# Pico-2-Max.net
KiCad netlist of a schematic drawn in EasyEDA Pro
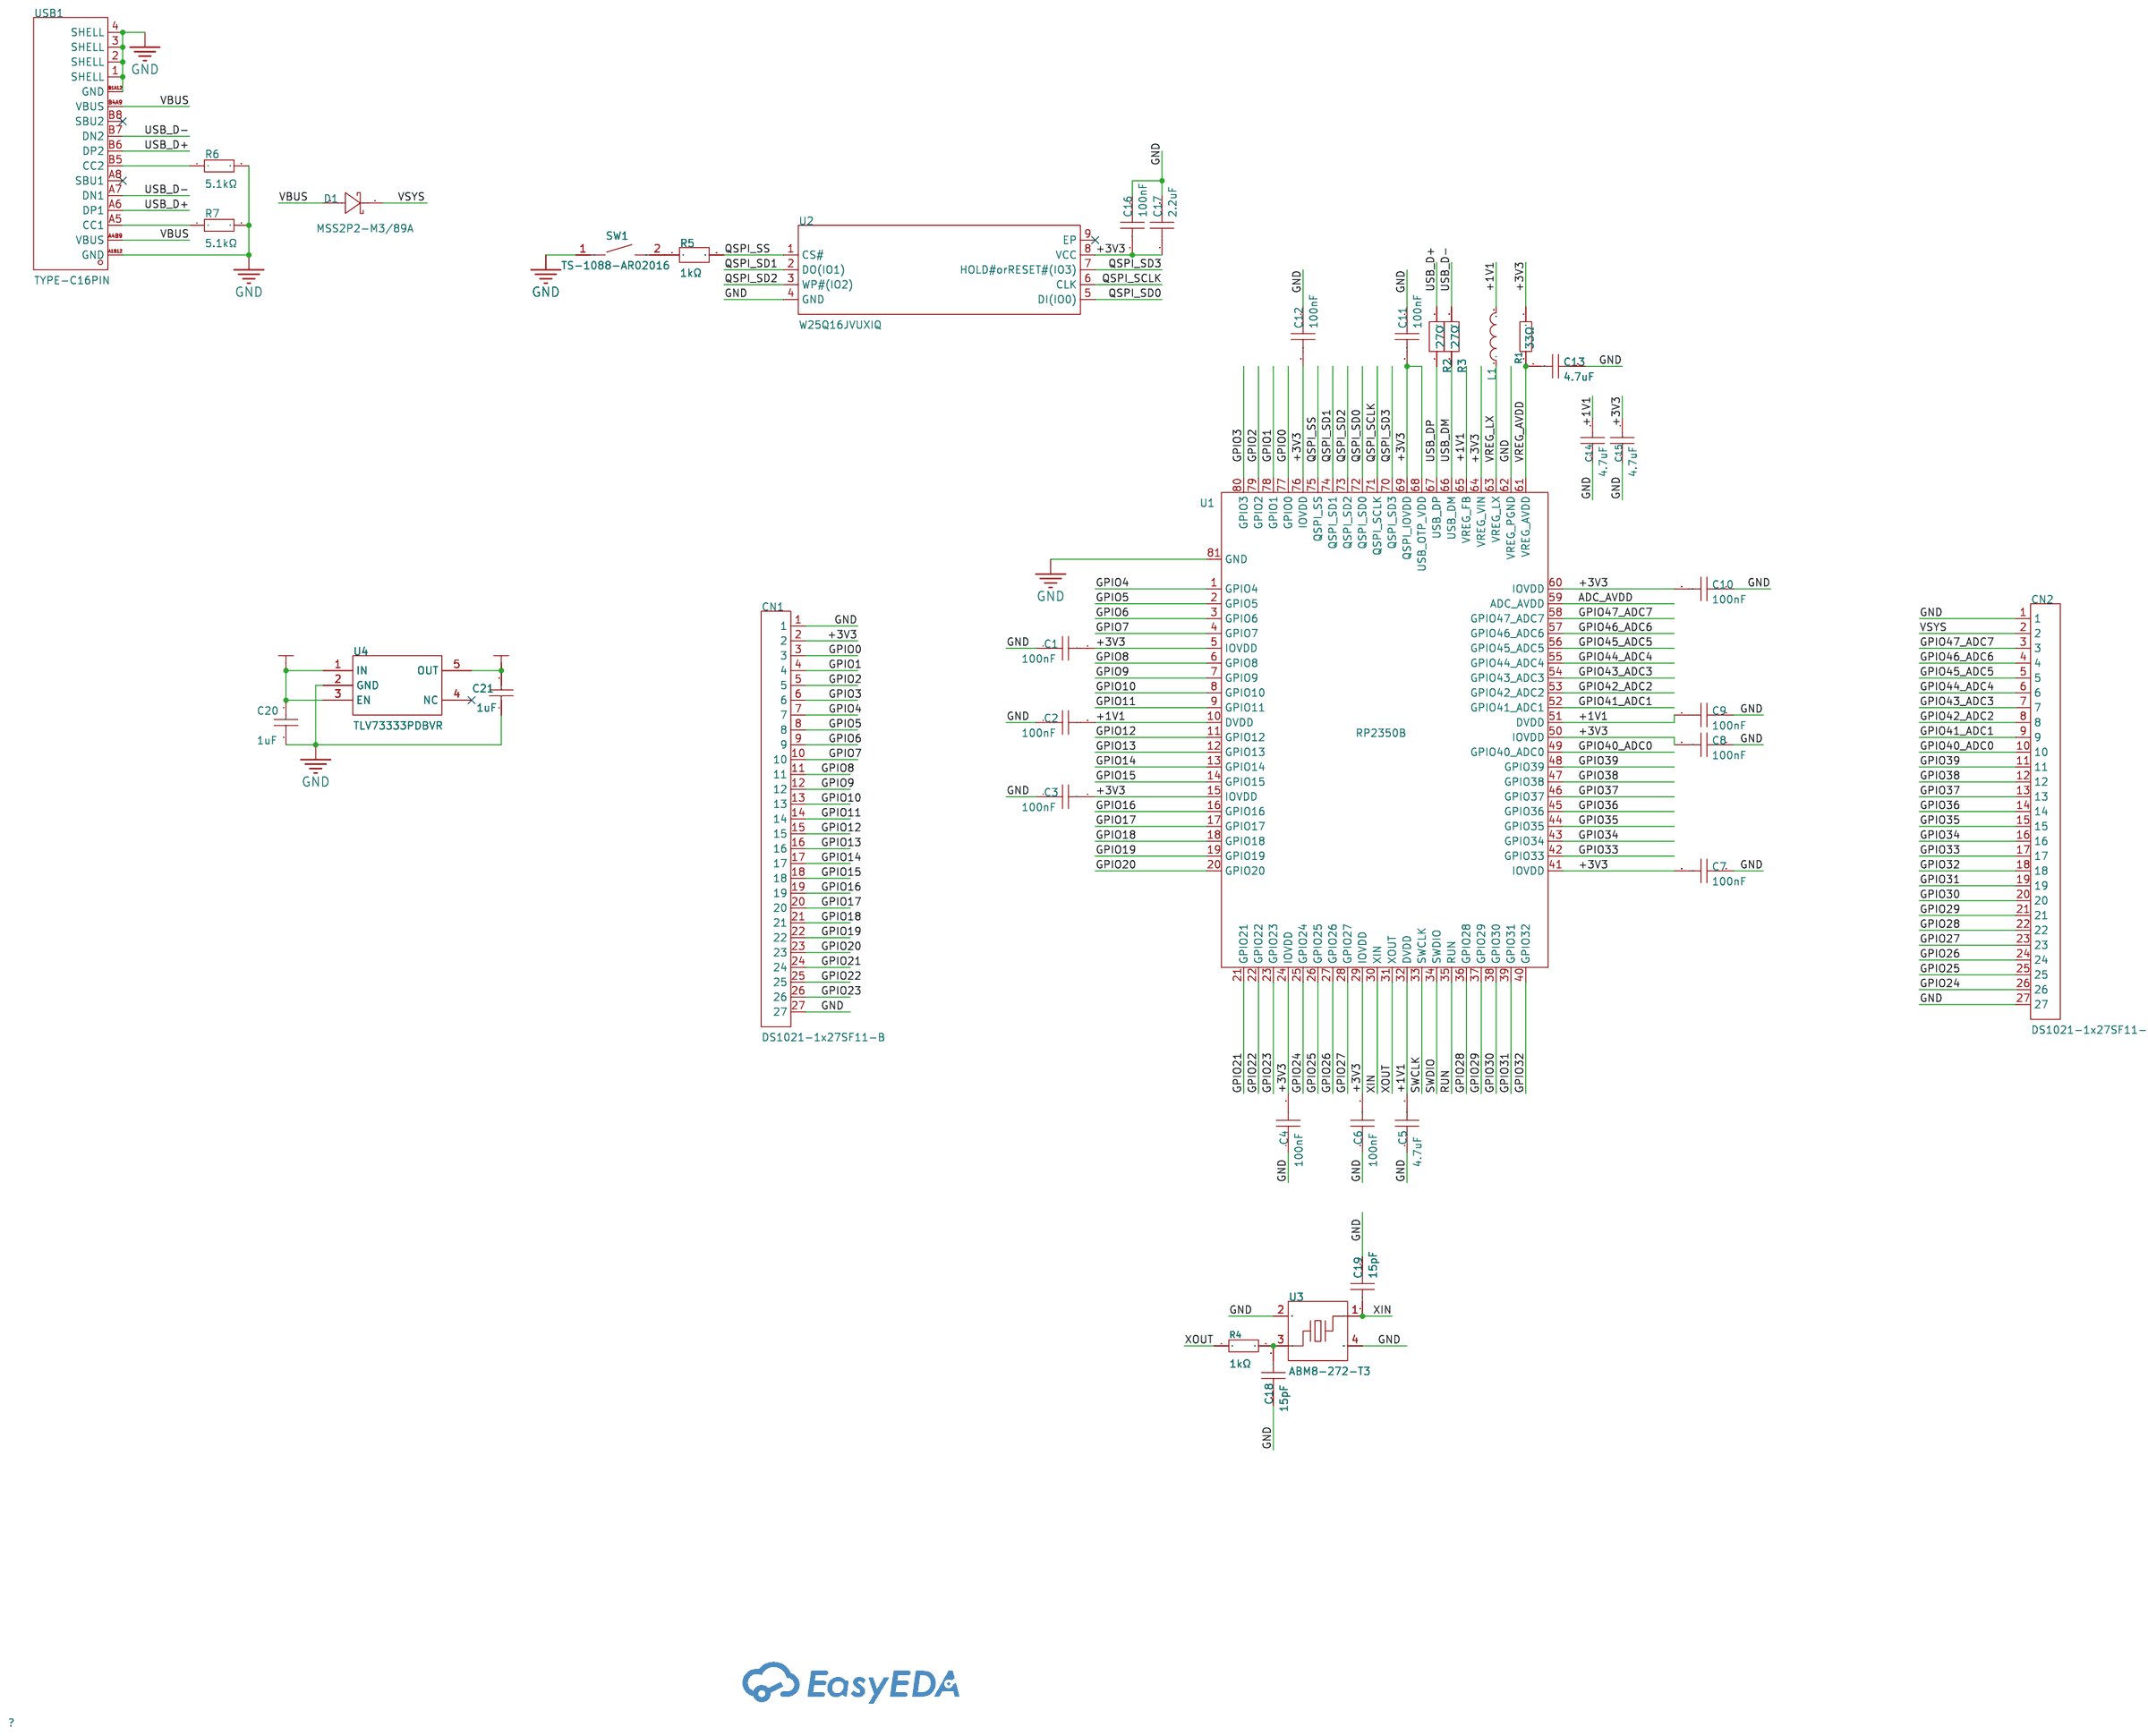
[diagram p0: schematic sheet]

(export (version "E")
  (design (tool "Eeschema 10.0.6"))
  (components
    (comp (ref "C1")
      (value "100nF")
      (footprint "easyedapro:C0201")
      (fields
        (field (name "Manufacturer Part") "GRM033R60J104KE19D")
        (field (name "Manufacturer") "muRata(村田)")
      )
      (libsource (lib "easyedapro") (part "GRM033R60J104KE19D"))
    )
    (comp (ref "C2")
      (value "100nF")
      (footprint "easyedapro:C0201")
      (fields
        (field (name "Manufacturer Part") "GRM033R60J104KE19D")
        (field (name "Manufacturer") "muRata(村田)")
      )
      (libsource (lib "easyedapro") (part "GRM033R60J104KE19D"))
    )
    (comp (ref "C3")
      (value "100nF")
      (footprint "easyedapro:C0201")
      (fields
        (field (name "Manufacturer Part") "GRM033R60J104KE19D")
        (field (name "Manufacturer") "muRata(村田)")
      )
      (libsource (lib "easyedapro") (part "GRM033R60J104KE19D"))
    )
    (comp (ref "C4")
      (value "100nF")
      (footprint "easyedapro:C0201")
      (fields
        (field (name "Manufacturer Part") "GRM033R60J104KE19D")
        (field (name "Manufacturer") "muRata(村田)")
      )
      (libsource (lib "easyedapro") (part "GRM033R60J104KE19D"))
    )
    (comp (ref "C5")
      (value "4.7uF")
      (footprint "easyedapro:C0201")
      (description "Capacitance:4.7uF Tolerance:±20% Tolerance:±20% Voltage Rating:6.3V Temperature Coefficient:X5R")
      (fields
        (field (name "Manufacturer Part") "GRM035R60J475ME15D")
        (field (name "Manufacturer") "muRata(村田)")
      )
      (libsource (lib "easyedapro") (part "GRM035R60J475ME15D"))
    )
    (comp (ref "C6")
      (value "100nF")
      (footprint "easyedapro:C0201")
      (fields
        (field (name "Manufacturer Part") "GRM033R60J104KE19D")
        (field (name "Manufacturer") "muRata(村田)")
      )
      (libsource (lib "easyedapro") (part "GRM033R60J104KE19D"))
    )
    (comp (ref "C7")
      (value "100nF")
      (footprint "easyedapro:C0201")
      (fields
        (field (name "Manufacturer Part") "GRM033R60J104KE19D")
        (field (name "Manufacturer") "muRata(村田)")
      )
      (libsource (lib "easyedapro") (part "GRM033R60J104KE19D"))
    )
    (comp (ref "C8")
      (value "100nF")
      (footprint "easyedapro:C0201")
      (fields
        (field (name "Manufacturer Part") "GRM033R60J104KE19D")
        (field (name "Manufacturer") "muRata(村田)")
      )
      (libsource (lib "easyedapro") (part "GRM033R60J104KE19D"))
    )
    (comp (ref "C9")
      (value "100nF")
      (footprint "easyedapro:C0201")
      (fields
        (field (name "Manufacturer Part") "GRM033R60J104KE19D")
        (field (name "Manufacturer") "muRata(村田)")
      )
      (libsource (lib "easyedapro") (part "GRM033R60J104KE19D"))
    )
    (comp (ref "C10")
      (value "100nF")
      (footprint "easyedapro:C0201")
      (fields
        (field (name "Manufacturer Part") "GRM033R60J104KE19D")
        (field (name "Manufacturer") "muRata(村田)")
      )
      (libsource (lib "easyedapro") (part "GRM033R60J104KE19D"))
    )
    (comp (ref "C11")
      (value "100nF")
      (footprint "easyedapro:C0201")
      (fields
        (field (name "Manufacturer Part") "GRM033R60J104KE19D")
        (field (name "Manufacturer") "muRata(村田)")
      )
      (libsource (lib "easyedapro") (part "GRM033R60J104KE19D"))
    )
    (comp (ref "C12")
      (value "100nF")
      (footprint "easyedapro:C0201")
      (fields
        (field (name "Manufacturer Part") "GRM033R60J104KE19D")
        (field (name "Manufacturer") "muRata(村田)")
      )
      (libsource (lib "easyedapro") (part "GRM033R60J104KE19D"))
    )
    (comp (ref "C13")
      (value "4.7uF")
      (footprint "easyedapro:C0201")
      (description "Capacitance:4.7uF Tolerance:±20% Tolerance:±20% Voltage Rating:6.3V Temperature Coefficient:X5R")
      (fields
        (field (name "Manufacturer Part") "GRM035R60J475ME15D")
        (field (name "Manufacturer") "muRata(村田)")
      )
      (libsource (lib "easyedapro") (part "GRM035R60J475ME15D"))
    )
    (comp (ref "C14")
      (value "4.7uF")
      (footprint "easyedapro:C0402")
      (description "Capacitance:4.7uF Tolerance:±20% Tolerance:±20% Voltage Rating:10V Temperature Coefficient:X5R")
      (fields
        (field (name "Manufacturer Part") "CL05A475MP5NRNC")
        (field (name "Manufacturer") "SAMSUNG(三星)")
      )
      (libsource (lib "easyedapro") (part "CL05A475MP5NRNC"))
    )
    (comp (ref "C15")
      (value "4.7uF")
      (footprint "easyedapro:C0402")
      (description "Capacitance:4.7uF Tolerance:±20% Tolerance:±20% Voltage Rating:10V Temperature Coefficient:X5R")
      (fields
        (field (name "Manufacturer Part") "CL05A475MP5NRNC")
        (field (name "Manufacturer") "SAMSUNG(三星)")
      )
      (libsource (lib "easyedapro") (part "CL05A475MP5NRNC"))
    )
    (comp (ref "C16")
      (value "100nF")
      (footprint "easyedapro:C0201")
      (fields
        (field (name "Manufacturer Part") "GRM033R60J104KE19D")
        (field (name "Manufacturer") "muRata(村田)")
      )
      (libsource (lib "easyedapro") (part "GRM033R60J104KE19D"))
    )
    (comp (ref "C17")
      (value "2.2uF")
      (footprint "easyedapro:C0201")
      (description "Capacitance:2.2uF Tolerance:±20% Tolerance:±20% Voltage Rating:6.3V Temperature Coefficient:X5R")
      (fields (field (name "Manufacturer Part") "0201X225M6R3NT") (field (name "Manufacturer") "FH(风华)"))
      (libsource (lib "easyedapro") (part "0201X225M6R3NT"))
    )
    (comp (ref "C18")
      (value "15pF")
      (footprint "easyedapro:C0201")
      (fields
        (field (name "Manufacturer Part") "CC0201JRNPO9BN150")
        (field (name "Manufacturer") "YAGEO(国巨)")
      )
      (libsource (lib "easyedapro") (part "CC0201JRNPO9BN150"))
    )
    (comp (ref "C19")
      (value "15pF")
      (footprint "easyedapro:C0201")
      (fields
        (field (name "Manufacturer Part") "CC0201JRNPO9BN150")
        (field (name "Manufacturer") "YAGEO(国巨)")
      )
      (libsource (lib "easyedapro") (part "CC0201JRNPO9BN150"))
    )
    (comp (ref "C20")
      (value "1uF")
      (footprint "easyedapro:C0201")
      (description "Capacitance:1uF Tolerance:±20% Tolerance:±20% Voltage Rating:6.3V Temperature Coefficient:X5R")
      (fields
        (field (name "Manufacturer Part") "CL03A105MQ3CSNH")
        (field (name "Manufacturer") "SAMSUNG(三星)")
      )
      (libsource (lib "easyedapro") (part "CL03A105MQ3CSNH"))
    )
    (comp (ref "C21")
      (value "1uF")
      (footprint "easyedapro:C0201")
      (description "Capacitance:1uF Tolerance:±20% Tolerance:±20% Voltage Rating:6.3V Temperature Coefficient:X5R")
      (fields
        (field (name "Manufacturer Part") "CL03A105MQ3CSNH")
        (field (name "Manufacturer") "SAMSUNG(三星)")
      )
      (libsource (lib "easyedapro") (part "CL03A105MQ3CSNH"))
    )
    (comp (ref "CN1")
      (value "DS1021-1x27SF11-B")
      (footprint "easyedapro:HDR-TH_27P-P2.54-V-M")
      (fields (field (name "Manufacturer") "CONNFLY"))
      (libsource (lib "easyedapro") (part "DS1021-1X27SF11-B"))
    )
    (comp (ref "CN2")
      (value "DS1021-1x27SF11-B")
      (footprint "easyedapro:HDR-TH_27P-P2.54-V-M")
      (fields (field (name "Manufacturer") "CONNFLY"))
      (libsource (lib "easyedapro") (part "DS1021-1X27SF11-B"))
    )
    (comp (ref "D1")
      (value "MSS2P2-M3/89A")
      (footprint "easyedapro:DO-219AD_L2.2-W1.3-L-RD_MSS2P2-M3-89A")
      (fields (field (name "Manufacturer") "VISHAY(威世)"))
      (libsource (lib "easyedapro") (part "MSS2P2-M3/89A"))
    )
    (comp (ref "L1")
      (value "AOTA-B201610S3R3-101-T")
      (footprint "easyedapro:IND-SMD_L2.0-W1.6_AOTA-B201610S3R3-101-T")
      (fields (field (name "Manufacturer") "ABRACON"))
      (libsource (lib "easyedapro") (part "AOTA-B201610S3R3-101-T"))
    )
    (comp (ref "R1")
      (value "33Ω")
      (footprint "easyedapro:R0201")
      (fields
        (field (name "Manufacturer Part") "0201WMJ0330TEE")
        (field (name "Manufacturer") "UNI-ROYAL(厚声)")
      )
      (libsource (lib "easyedapro") (part "0201WMJ0330TEE"))
    )
    (comp (ref "R2")
      (value "27Ω")
      (footprint "easyedapro:R0201")
      (fields
        (field (name "Manufacturer Part") "0201WMF270JTEE")
        (field (name "Manufacturer") "UNI-ROYAL(厚声)")
      )
      (libsource (lib "easyedapro") (part "0201WMF270JTEE"))
    )
    (comp (ref "R3")
      (value "27Ω")
      (footprint "easyedapro:R0201")
      (fields
        (field (name "Manufacturer Part") "0201WMF270JTEE")
        (field (name "Manufacturer") "UNI-ROYAL(厚声)")
      )
      (libsource (lib "easyedapro") (part "0201WMF270JTEE"))
    )
    (comp (ref "R4")
      (value "1kΩ")
      (footprint "easyedapro:R0201")
      (fields (field (name "Manufacturer Part") "RTT01102JTH") (field (name "Manufacturer") "RALEC(旺诠)"))
      (libsource (lib "easyedapro") (part "RTT01102JTH"))
    )
    (comp (ref "R5")
      (value "1kΩ")
      (footprint "easyedapro:R0201")
      (fields (field (name "Manufacturer Part") "FRC0201F1001TS") (field (name "Manufacturer") "FOJAN(富捷)"))
      (libsource (lib "easyedapro") (part "FRC0201F1001TS"))
    )
    (comp (ref "R6")
      (value "5.1kΩ")
      (footprint "easyedapro:R0201")
      (fields (field (name "Manufacturer Part") "RC0201FR-075K1L") (field (name "Manufacturer") "YAGEO(国巨)"))
      (libsource (lib "easyedapro") (part "RC0201FR-075K1L"))
    )
    (comp (ref "R7")
      (value "5.1kΩ")
      (footprint "easyedapro:R0201")
      (fields (field (name "Manufacturer Part") "RC0201FR-075K1L") (field (name "Manufacturer") "YAGEO(国巨)"))
      (libsource (lib "easyedapro") (part "RC0201FR-075K1L"))
    )
    (comp (ref "SW1")
      (value "TS-1088-AR02016")
      (footprint "easyedapro:SW-SMD_L3.9-W3.0-P4.45")
      (fields (field (name "Manufacturer") "XUNPU(讯普)"))
      (libsource (lib "easyedapro") (part "TS-1088-AR02016"))
    )
    (comp (ref "U1")
      (value "RP2350B")
      (footprint "easyedapro:QFN-80_L10.0-W10.0-P0.40-TL-EP3.4")
      (fields (field (name "Manufacturer") "Raspberry Pi(树莓派)"))
      (libsource (lib "easyedapro") (part "RP2350B_C42415655"))
    )
    (comp (ref "U2")
      (value "W25Q16JVUXIQ")
      (footprint "easyedapro:USON-8_L3.0-W2.0-P0.50-BL-EP")
      (fields (field (name "Manufacturer") "Winbond(华邦)"))
      (libsource (lib "easyedapro") (part "W25Q16JVUXIQ"))
    )
    (comp (ref "U3")
      (value "ABM8-272-T3")
      (footprint "easyedapro:CRYSTAL-SMD_4P-L3.2-W2.5-BL")
      (fields (field (name "Manufacturer") "ABRACON"))
      (libsource (lib "easyedapro") (part "ABM8-272-T3_C20625731"))
    )
    (comp (ref "U4")
      (value "TLV73333PDBVR")
      (footprint "easyedapro:SOT-23-5_L3.0-W1.7-P0.95-LS2.8-BR")
      (fields (field (name "Manufacturer") "TI(德州仪器)"))
      (libsource (lib "easyedapro") (part "TLV73333PDBVR"))
    )
    (comp (ref "USB1")
      (value "TYPE-C16PIN")
      (footprint "easyedapro:USB-C-SMD_TYPE-C16PIN")
      (fields (field (name "Manufacturer") "SHOU HAN(首韩)"))
      (libsource (lib "easyedapro") (part "TYPE-C16PIN"))
    )
  )
  (nets
    (net (code "1") (name "+3V3") (class "Default")
      (node (ref "C1") (pin "2") (pinfunction "2_2") (pintype "unspecified"))
      (node (ref "C10") (pin "2") (pinfunction "2_2") (pintype "unspecified"))
      (node (ref "C11") (pin "2") (pinfunction "2_2") (pintype "unspecified"))
      (node (ref "C12") (pin "2") (pinfunction "2_2") (pintype "unspecified"))
      (node (ref "C15") (pin "2") (pinfunction "2_2") (pintype "input"))
      (node (ref "C16") (pin "2") (pinfunction "2_2") (pintype "unspecified"))
      (node (ref "C17") (pin "1") (pinfunction "1_1") (pintype "unspecified"))
      (node (ref "C21") (pin "2") (pinfunction "2_2") (pintype "input"))
      (node (ref "C3") (pin "2") (pinfunction "2_2") (pintype "unspecified"))
      (node (ref "C4") (pin "2") (pinfunction "2_2") (pintype "unspecified"))
      (node (ref "C6") (pin "2") (pinfunction "2_2") (pintype "unspecified"))
      (node (ref "C7") (pin "2") (pinfunction "2_2") (pintype "unspecified"))
      (node (ref "C8") (pin "2") (pinfunction "2_2") (pintype "unspecified"))
      (node (ref "CN1") (pin "2") (pinfunction "2_2") (pintype "unspecified"))
      (node (ref "R1") (pin "2") (pinfunction "2_2") (pintype "input"))
      (node (ref "U1") (pin "15") (pinfunction "IOVDD_15") (pintype "unspecified"))
      (node (ref "U1") (pin "24") (pinfunction "IOVDD_24") (pintype "unspecified"))
      (node (ref "U1") (pin "29") (pinfunction "IOVDD_29") (pintype "unspecified"))
      (node (ref "U1") (pin "41") (pinfunction "IOVDD_41") (pintype "unspecified"))
      (node (ref "U1") (pin "5") (pinfunction "IOVDD_5") (pintype "unspecified"))
      (node (ref "U1") (pin "50") (pinfunction "IOVDD_50") (pintype "unspecified"))
      (node (ref "U1") (pin "60") (pinfunction "IOVDD_60") (pintype "unspecified"))
      (node (ref "U1") (pin "64") (pinfunction "VREG_VIN_64") (pintype "unspecified"))
      (node (ref "U1") (pin "68") (pinfunction "USB_OTP_VDD_68") (pintype "unspecified"))
      (node (ref "U1") (pin "69") (pinfunction "QSPI_IOVDD_69") (pintype "unspecified"))
      (node (ref "U1") (pin "76") (pinfunction "IOVDD_76") (pintype "unspecified"))
      (node (ref "U2") (pin "8") (pinfunction "VCC_8") (pintype "unspecified"))
      (node (ref "U4") (pin "5") (pinfunction "OUT_5") (pintype "unspecified"))
    )
    (net (code "2") (name "/+1V1") (class "Default")
      (node (ref "C14") (pin "2") (pinfunction "2_2") (pintype "input"))
      (node (ref "C2") (pin "2") (pinfunction "2_2") (pintype "unspecified"))
      (node (ref "C5") (pin "2") (pinfunction "2_2") (pintype "unspecified"))
      (node (ref "C9") (pin "2") (pinfunction "2_2") (pintype "unspecified"))
      (node (ref "L1") (pin "2") (pinfunction "2_2") (pintype "unspecified"))
      (node (ref "U1") (pin "10") (pinfunction "DVDD_10") (pintype "unspecified"))
      (node (ref "U1") (pin "32") (pinfunction "DVDD_32") (pintype "unspecified"))
      (node (ref "U1") (pin "51") (pinfunction "DVDD_51") (pintype "unspecified"))
      (node (ref "U1") (pin "65") (pinfunction "VREG_FB_65") (pintype "unspecified"))
    )
    (net (code "3") (name "/ADC_AVDD") (class "Default")
      (node (ref "U1") (pin "59") (pinfunction "ADC_AVDD_59") (pintype "unspecified"))
    )
    (net (code "4") (name "/GPIO0") (class "Default")
      (node (ref "CN1") (pin "3") (pinfunction "3_3") (pintype "unspecified"))
      (node (ref "U1") (pin "77") (pinfunction "GPIO0_77") (pintype "unspecified"))
    )
    (net (code "5") (name "/GPIO1") (class "Default")
      (node (ref "CN1") (pin "4") (pinfunction "4_4") (pintype "unspecified"))
      (node (ref "U1") (pin "78") (pinfunction "GPIO1_78") (pintype "unspecified"))
    )
    (net (code "6") (name "/GPIO2") (class "Default")
      (node (ref "CN1") (pin "5") (pinfunction "5_5") (pintype "unspecified"))
      (node (ref "U1") (pin "79") (pinfunction "GPIO2_79") (pintype "unspecified"))
    )
    (net (code "7") (name "/GPIO3") (class "Default")
      (node (ref "CN1") (pin "6") (pinfunction "6_6") (pintype "unspecified"))
      (node (ref "U1") (pin "80") (pinfunction "GPIO3_80") (pintype "unspecified"))
    )
    (net (code "8") (name "/GPIO4") (class "Default")
      (node (ref "CN1") (pin "7") (pinfunction "7_7") (pintype "unspecified"))
      (node (ref "U1") (pin "1") (pinfunction "GPIO4_1") (pintype "unspecified"))
    )
    (net (code "9") (name "/GPIO5") (class "Default")
      (node (ref "CN1") (pin "8") (pinfunction "8_8") (pintype "unspecified"))
      (node (ref "U1") (pin "2") (pinfunction "GPIO5_2") (pintype "unspecified"))
    )
    (net (code "10") (name "/GPIO6") (class "Default")
      (node (ref "CN1") (pin "9") (pinfunction "9_9") (pintype "unspecified"))
      (node (ref "U1") (pin "3") (pinfunction "GPIO6_3") (pintype "unspecified"))
    )
    (net (code "11") (name "/GPIO7") (class "Default")
      (node (ref "CN1") (pin "10") (pinfunction "10_10") (pintype "unspecified"))
      (node (ref "U1") (pin "4") (pinfunction "GPIO7_4") (pintype "unspecified"))
    )
    (net (code "12") (name "/GPIO8") (class "Default")
      (node (ref "CN1") (pin "11") (pinfunction "11_11") (pintype "unspecified"))
      (node (ref "U1") (pin "6") (pinfunction "GPIO8_6") (pintype "unspecified"))
    )
    (net (code "13") (name "/GPIO9") (class "Default")
      (node (ref "CN1") (pin "12") (pinfunction "12_12") (pintype "unspecified"))
      (node (ref "U1") (pin "7") (pinfunction "GPIO9_7") (pintype "unspecified"))
    )
    (net (code "14") (name "/GPIO10") (class "Default")
      (node (ref "CN1") (pin "13") (pinfunction "13_13") (pintype "unspecified"))
      (node (ref "U1") (pin "8") (pinfunction "GPIO10_8") (pintype "unspecified"))
    )
    (net (code "15") (name "/GPIO11") (class "Default")
      (node (ref "CN1") (pin "14") (pinfunction "14_14") (pintype "unspecified"))
      (node (ref "U1") (pin "9") (pinfunction "GPIO11_9") (pintype "unspecified"))
    )
    (net (code "16") (name "/GPIO12") (class "Default")
      (node (ref "CN1") (pin "15") (pinfunction "15_15") (pintype "unspecified"))
      (node (ref "U1") (pin "11") (pinfunction "GPIO12_11") (pintype "unspecified"))
    )
    (net (code "17") (name "/GPIO13") (class "Default")
      (node (ref "CN1") (pin "16") (pinfunction "16_16") (pintype "unspecified"))
      (node (ref "U1") (pin "12") (pinfunction "GPIO13_12") (pintype "unspecified"))
    )
    (net (code "18") (name "/GPIO14") (class "Default")
      (node (ref "CN1") (pin "17") (pinfunction "17_17") (pintype "unspecified"))
      (node (ref "U1") (pin "13") (pinfunction "GPIO14_13") (pintype "unspecified"))
    )
    (net (code "19") (name "/GPIO15") (class "Default")
      (node (ref "CN1") (pin "18") (pinfunction "18_18") (pintype "unspecified"))
      (node (ref "U1") (pin "14") (pinfunction "GPIO15_14") (pintype "unspecified"))
    )
    (net (code "20") (name "/GPIO16") (class "Default")
      (node (ref "CN1") (pin "19") (pinfunction "19_19") (pintype "unspecified"))
      (node (ref "U1") (pin "16") (pinfunction "GPIO16_16") (pintype "unspecified"))
    )
    (net (code "21") (name "/GPIO17") (class "Default")
      (node (ref "CN1") (pin "20") (pinfunction "20_20") (pintype "unspecified"))
      (node (ref "U1") (pin "17") (pinfunction "GPIO17_17") (pintype "unspecified"))
    )
    (net (code "22") (name "/GPIO18") (class "Default")
      (node (ref "CN1") (pin "21") (pinfunction "21_21") (pintype "unspecified"))
      (node (ref "U1") (pin "18") (pinfunction "GPIO18_18") (pintype "unspecified"))
    )
    (net (code "23") (name "/GPIO19") (class "Default")
      (node (ref "CN1") (pin "22") (pinfunction "22_22") (pintype "unspecified"))
      (node (ref "U1") (pin "19") (pinfunction "GPIO19_19") (pintype "unspecified"))
    )
    (net (code "24") (name "/GPIO20") (class "Default")
      (node (ref "CN1") (pin "23") (pinfunction "23_23") (pintype "unspecified"))
      (node (ref "U1") (pin "20") (pinfunction "GPIO20_20") (pintype "unspecified"))
    )
    (net (code "25") (name "/GPIO21") (class "Default")
      (node (ref "CN1") (pin "24") (pinfunction "24_24") (pintype "unspecified"))
      (node (ref "U1") (pin "21") (pinfunction "GPIO21_21") (pintype "unspecified"))
    )
    (net (code "26") (name "/GPIO22") (class "Default")
      (node (ref "CN1") (pin "25") (pinfunction "25_25") (pintype "unspecified"))
      (node (ref "U1") (pin "22") (pinfunction "GPIO22_22") (pintype "unspecified"))
    )
    (net (code "27") (name "/GPIO23") (class "Default")
      (node (ref "CN1") (pin "26") (pinfunction "26_26") (pintype "unspecified"))
      (node (ref "U1") (pin "23") (pinfunction "GPIO23_23") (pintype "unspecified"))
    )
    (net (code "28") (name "/GPIO24") (class "Default")
      (node (ref "CN2") (pin "26") (pinfunction "26_26") (pintype "unspecified"))
      (node (ref "U1") (pin "25") (pinfunction "GPIO24_25") (pintype "unspecified"))
    )
    (net (code "29") (name "/GPIO25") (class "Default")
      (node (ref "CN2") (pin "25") (pinfunction "25_25") (pintype "unspecified"))
      (node (ref "U1") (pin "26") (pinfunction "GPIO25_26") (pintype "unspecified"))
    )
    (net (code "30") (name "/GPIO26") (class "Default")
      (node (ref "CN2") (pin "24") (pinfunction "24_24") (pintype "unspecified"))
      (node (ref "U1") (pin "27") (pinfunction "GPIO26_27") (pintype "unspecified"))
    )
    (net (code "31") (name "/GPIO27") (class "Default")
      (node (ref "CN2") (pin "23") (pinfunction "23_23") (pintype "unspecified"))
      (node (ref "U1") (pin "28") (pinfunction "GPIO27_28") (pintype "unspecified"))
    )
    (net (code "32") (name "/GPIO28") (class "Default")
      (node (ref "CN2") (pin "22") (pinfunction "22_22") (pintype "unspecified"))
      (node (ref "U1") (pin "36") (pinfunction "GPIO28_36") (pintype "unspecified"))
    )
    (net (code "33") (name "/GPIO29") (class "Default")
      (node (ref "CN2") (pin "21") (pinfunction "21_21") (pintype "unspecified"))
      (node (ref "U1") (pin "37") (pinfunction "GPIO29_37") (pintype "unspecified"))
    )
    (net (code "34") (name "/GPIO30") (class "Default")
      (node (ref "CN2") (pin "20") (pinfunction "20_20") (pintype "unspecified"))
      (node (ref "U1") (pin "38") (pinfunction "GPIO30_38") (pintype "unspecified"))
    )
    (net (code "35") (name "/GPIO31") (class "Default")
      (node (ref "CN2") (pin "19") (pinfunction "19_19") (pintype "unspecified"))
      (node (ref "U1") (pin "39") (pinfunction "GPIO31_39") (pintype "unspecified"))
    )
    (net (code "36") (name "/GPIO32") (class "Default")
      (node (ref "CN2") (pin "18") (pinfunction "18_18") (pintype "unspecified"))
      (node (ref "U1") (pin "40") (pinfunction "GPIO32_40") (pintype "unspecified"))
    )
    (net (code "37") (name "/GPIO33") (class "Default")
      (node (ref "CN2") (pin "17") (pinfunction "17_17") (pintype "unspecified"))
      (node (ref "U1") (pin "42") (pinfunction "GPIO33_42") (pintype "unspecified"))
    )
    (net (code "38") (name "/GPIO34") (class "Default")
      (node (ref "CN2") (pin "16") (pinfunction "16_16") (pintype "unspecified"))
      (node (ref "U1") (pin "43") (pinfunction "GPIO34_43") (pintype "unspecified"))
    )
    (net (code "39") (name "/GPIO35") (class "Default")
      (node (ref "CN2") (pin "15") (pinfunction "15_15") (pintype "unspecified"))
      (node (ref "U1") (pin "44") (pinfunction "GPIO35_44") (pintype "unspecified"))
    )
    (net (code "40") (name "/GPIO36") (class "Default")
      (node (ref "CN2") (pin "14") (pinfunction "14_14") (pintype "unspecified"))
      (node (ref "U1") (pin "45") (pinfunction "GPIO36_45") (pintype "unspecified"))
    )
    (net (code "41") (name "/GPIO37") (class "Default")
      (node (ref "CN2") (pin "13") (pinfunction "13_13") (pintype "unspecified"))
      (node (ref "U1") (pin "46") (pinfunction "GPIO37_46") (pintype "unspecified"))
    )
    (net (code "42") (name "/GPIO38") (class "Default")
      (node (ref "CN2") (pin "12") (pinfunction "12_12") (pintype "unspecified"))
      (node (ref "U1") (pin "47") (pinfunction "GPIO38_47") (pintype "unspecified"))
    )
    (net (code "43") (name "/GPIO39") (class "Default")
      (node (ref "CN2") (pin "11") (pinfunction "11_11") (pintype "unspecified"))
      (node (ref "U1") (pin "48") (pinfunction "GPIO39_48") (pintype "unspecified"))
    )
    (net (code "44") (name "/GPIO40_ADC0") (class "Default")
      (node (ref "CN2") (pin "10") (pinfunction "10_10") (pintype "unspecified"))
      (node (ref "U1") (pin "49") (pinfunction "GPIO40_ADC0_49") (pintype "unspecified"))
    )
    (net (code "45") (name "/GPIO41_ADC1") (class "Default")
      (node (ref "CN2") (pin "9") (pinfunction "9_9") (pintype "unspecified"))
      (node (ref "U1") (pin "52") (pinfunction "GPIO41_ADC1_52") (pintype "unspecified"))
    )
    (net (code "46") (name "/GPIO42_ADC2") (class "Default")
      (node (ref "CN2") (pin "8") (pinfunction "8_8") (pintype "unspecified"))
      (node (ref "U1") (pin "53") (pinfunction "GPIO42_ADC2_53") (pintype "unspecified"))
    )
    (net (code "47") (name "/GPIO43_ADC3") (class "Default")
      (node (ref "CN2") (pin "7") (pinfunction "7_7") (pintype "unspecified"))
      (node (ref "U1") (pin "54") (pinfunction "GPIO43_ADC3_54") (pintype "unspecified"))
    )
    (net (code "48") (name "/GPIO44_ADC4") (class "Default")
      (node (ref "CN2") (pin "6") (pinfunction "6_6") (pintype "unspecified"))
      (node (ref "U1") (pin "55") (pinfunction "GPIO44_ADC4_55") (pintype "unspecified"))
    )
    (net (code "49") (name "/GPIO45_ADC5") (class "Default")
      (node (ref "CN2") (pin "5") (pinfunction "5_5") (pintype "unspecified"))
      (node (ref "U1") (pin "56") (pinfunction "GPIO45_ADC5_56") (pintype "unspecified"))
    )
    (net (code "50") (name "/GPIO46_ADC6") (class "Default")
      (node (ref "CN2") (pin "4") (pinfunction "4_4") (pintype "unspecified"))
      (node (ref "U1") (pin "57") (pinfunction "GPIO46_ADC6_57") (pintype "unspecified"))
    )
    (net (code "51") (name "/GPIO47_ADC7") (class "Default")
      (node (ref "CN2") (pin "3") (pinfunction "3_3") (pintype "unspecified"))
      (node (ref "U1") (pin "58") (pinfunction "GPIO47_ADC7_58") (pintype "unspecified"))
    )
    (net (code "52") (name "/QSPI_SCLK") (class "Default")
      (node (ref "U1") (pin "71") (pinfunction "QSPI_SCLK_71") (pintype "unspecified"))
      (node (ref "U2") (pin "6") (pinfunction "CLK_6") (pintype "unspecified"))
    )
    (net (code "53") (name "/QSPI_SD0") (class "Default")
      (node (ref "U1") (pin "72") (pinfunction "QSPI_SD0_72") (pintype "unspecified"))
      (node (ref "U2") (pin "5") (pinfunction "DI(IO0)_5") (pintype "unspecified"))
    )
    (net (code "54") (name "/QSPI_SD1") (class "Default")
      (node (ref "U1") (pin "74") (pinfunction "QSPI_SD1_74") (pintype "unspecified"))
      (node (ref "U2") (pin "2") (pinfunction "DO(IO1)_2") (pintype "unspecified"))
    )
    (net (code "55") (name "/QSPI_SD2") (class "Default")
      (node (ref "U1") (pin "73") (pinfunction "QSPI_SD2_73") (pintype "unspecified"))
      (node (ref "U2") (pin "3") (pinfunction "WP#(IO2)_3") (pintype "unspecified"))
    )
    (net (code "56") (name "/QSPI_SD3") (class "Default")
      (node (ref "U1") (pin "70") (pinfunction "QSPI_SD3_70") (pintype "unspecified"))
      (node (ref "U2") (pin "7") (pinfunction "HOLD#orRESET#(IO3)_7") (pintype "unspecified"))
    )
    (net (code "57") (name "/QSPI_SS") (class "Default")
      (node (ref "R5") (pin "2") (pinfunction "2_2") (pintype "unspecified"))
      (node (ref "U1") (pin "75") (pinfunction "QSPI_SS_75") (pintype "unspecified"))
      (node (ref "U2") (pin "1") (pinfunction "CS#_1") (pintype "unspecified"))
    )
    (net (code "58") (name "/RUN") (class "Default")
      (node (ref "U1") (pin "35") (pinfunction "RUN_35") (pintype "unspecified"))
    )
    (net (code "59") (name "/SWCLK") (class "Default")
      (node (ref "U1") (pin "33") (pinfunction "SWCLK_33") (pintype "unspecified"))
    )
    (net (code "60") (name "/SWDIO") (class "Default")
      (node (ref "U1") (pin "34") (pinfunction "SWDIO_34") (pintype "unspecified"))
    )
    (net (code "61") (name "/USB_D+") (class "Default")
      (node (ref "R2") (pin "2") (pinfunction "2_2") (pintype "unspecified"))
      (node (ref "USB1") (pin "A6") (pinfunction "DP1_A6") (pintype "unspecified"))
      (node (ref "USB1") (pin "B6") (pinfunction "DP2_B6") (pintype "unspecified"))
    )
    (net (code "62") (name "/USB_D-") (class "Default")
      (node (ref "R3") (pin "2") (pinfunction "2_2") (pintype "unspecified"))
      (node (ref "USB1") (pin "A7") (pinfunction "DN1_A7") (pintype "unspecified"))
      (node (ref "USB1") (pin "B7") (pinfunction "DN2_B7") (pintype "unspecified"))
    )
    (net (code "63") (name "/USB_DM") (class "Default")
      (node (ref "R3") (pin "1") (pinfunction "1_1") (pintype "unspecified"))
      (node (ref "U1") (pin "66") (pinfunction "USB_DM_66") (pintype "unspecified"))
    )
    (net (code "64") (name "/USB_DP") (class "Default")
      (node (ref "R2") (pin "1") (pinfunction "1_1") (pintype "unspecified"))
      (node (ref "U1") (pin "67") (pinfunction "USB_DP_67") (pintype "unspecified"))
    )
    (net (code "65") (name "/VBUS") (class "Default")
      (node (ref "D1") (pin "2") (pinfunction "A_2") (pintype "unspecified"))
      (node (ref "USB1") (pin "A4B9") (pinfunction "VBUS_A4B9") (pintype "unspecified"))
      (node (ref "USB1") (pin "B4A9") (pinfunction "VBUS_B4A9") (pintype "unspecified"))
    )
    (net (code "66") (name "/VREG_AVDD") (class "Default")
      (node (ref "C13") (pin "2") (pinfunction "2_2") (pintype "unspecified"))
      (node (ref "R1") (pin "1") (pinfunction "1_1") (pintype "input"))
      (node (ref "U1") (pin "61") (pinfunction "VREG_AVDD_61") (pintype "unspecified"))
    )
    (net (code "67") (name "/VREG_LX") (class "Default")
      (node (ref "L1") (pin "1") (pinfunction "1_1") (pintype "unspecified"))
      (node (ref "U1") (pin "63") (pinfunction "VREG_LX_63") (pintype "unspecified"))
    )
    (net (code "68") (name "/XIN") (class "Default")
      (node (ref "C19") (pin "1") (pinfunction "1_1") (pintype "unspecified"))
      (node (ref "U1") (pin "30") (pinfunction "XIN_30") (pintype "unspecified"))
      (node (ref "U3") (pin "1") (pinfunction "1_1") (pintype "input"))
    )
    (net (code "69") (name "/XOUT") (class "Default")
      (node (ref "R4") (pin "1") (pinfunction "1_1") (pintype "input"))
      (node (ref "U1") (pin "31") (pinfunction "XOUT_31") (pintype "unspecified"))
    )
    (net (code "70") (name "GND") (class "Default")
      (node (ref "C1") (pin "1") (pinfunction "1_1") (pintype "unspecified"))
      (node (ref "C10") (pin "1") (pinfunction "1_1") (pintype "unspecified"))
      (node (ref "C11") (pin "1") (pinfunction "1_1") (pintype "unspecified"))
      (node (ref "C12") (pin "1") (pinfunction "1_1") (pintype "unspecified"))
      (node (ref "C13") (pin "1") (pinfunction "1_1") (pintype "unspecified"))
      (node (ref "C14") (pin "1") (pinfunction "1_1") (pintype "input"))
      (node (ref "C15") (pin "1") (pinfunction "1_1") (pintype "input"))
      (node (ref "C16") (pin "1") (pinfunction "1_1") (pintype "unspecified"))
      (node (ref "C17") (pin "2") (pinfunction "2_2") (pintype "unspecified"))
      (node (ref "C18") (pin "1") (pinfunction "1_1") (pintype "unspecified"))
      (node (ref "C19") (pin "2") (pinfunction "2_2") (pintype "unspecified"))
      (node (ref "C2") (pin "1") (pinfunction "1_1") (pintype "unspecified"))
      (node (ref "C20") (pin "1") (pinfunction "1_1") (pintype "input"))
      (node (ref "C21") (pin "1") (pinfunction "1_1") (pintype "input"))
      (node (ref "C3") (pin "1") (pinfunction "1_1") (pintype "unspecified"))
      (node (ref "C4") (pin "1") (pinfunction "1_1") (pintype "unspecified"))
      (node (ref "C5") (pin "1") (pinfunction "1_1") (pintype "unspecified"))
      (node (ref "C6") (pin "1") (pinfunction "1_1") (pintype "unspecified"))
      (node (ref "C7") (pin "1") (pinfunction "1_1") (pintype "unspecified"))
      (node (ref "C8") (pin "1") (pinfunction "1_1") (pintype "unspecified"))
      (node (ref "C9") (pin "1") (pinfunction "1_1") (pintype "unspecified"))
      (node (ref "CN1") (pin "1") (pinfunction "1_1") (pintype "unspecified"))
      (node (ref "CN1") (pin "27") (pinfunction "27_27") (pintype "unspecified"))
      (node (ref "CN2") (pin "1") (pinfunction "1_1") (pintype "unspecified"))
      (node (ref "CN2") (pin "27") (pinfunction "27_27") (pintype "unspecified"))
      (node (ref "R6") (pin "2") (pinfunction "2_2") (pintype "unspecified"))
      (node (ref "R7") (pin "2") (pinfunction "2_2") (pintype "unspecified"))
      (node (ref "SW1") (pin "1") (pinfunction "1_1") (pintype "unspecified"))
      (node (ref "U1") (pin "62") (pinfunction "VREG_PGND_62") (pintype "unspecified"))
      (node (ref "U1") (pin "81") (pinfunction "GND_81") (pintype "unspecified"))
      (node (ref "U2") (pin "4") (pinfunction "GND_4") (pintype "unspecified"))
      (node (ref "U3") (pin "2") (pinfunction "GND_2") (pintype "input"))
      (node (ref "U3") (pin "4") (pinfunction "GND_4") (pintype "input"))
      (node (ref "U4") (pin "2") (pinfunction "GND_2") (pintype "unspecified"))
      (node (ref "USB1") (pin "1") (pinfunction "SHELL_1") (pintype "unspecified"))
      (node (ref "USB1") (pin "2") (pinfunction "SHELL_2") (pintype "unspecified"))
      (node (ref "USB1") (pin "3") (pinfunction "SHELL_3") (pintype "unspecified"))
      (node (ref "USB1") (pin "4") (pinfunction "SHELL_4") (pintype "unspecified"))
      (node (ref "USB1") (pin "A1B12") (pinfunction "GND_A1B12") (pintype "unspecified"))
      (node (ref "USB1") (pin "B1A12") (pinfunction "GND_B1A12") (pintype "unspecified"))
    )
    (net (code "71") (name "Net-(C18-Pad2)") (class "Default")
      (node (ref "C18") (pin "2") (pinfunction "2_2") (pintype "unspecified"))
      (node (ref "R4") (pin "2") (pinfunction "2_2") (pintype "input"))
      (node (ref "U3") (pin "3") (pinfunction "3_3") (pintype "input"))
    )
    (net (code "72") (name "Net-(R5-Pad1)") (class "Default")
      (node (ref "R5") (pin "1") (pinfunction "1_1") (pintype "unspecified"))
      (node (ref "SW1") (pin "2") (pinfunction "2_2") (pintype "unspecified"))
    )
    (net (code "73") (name "Net-(USB1-CC1)") (class "Default")
      (node (ref "R7") (pin "1") (pinfunction "1_1") (pintype "unspecified"))
      (node (ref "USB1") (pin "A5") (pinfunction "CC1_A5") (pintype "unspecified"))
    )
    (net (code "74") (name "Net-(USB1-CC2)") (class "Default")
      (node (ref "R6") (pin "1") (pinfunction "1_1") (pintype "unspecified"))
      (node (ref "USB1") (pin "B5") (pinfunction "CC2_B5") (pintype "unspecified"))
    )
    (net (code "75") (name "VSYS") (class "Default")
      (node (ref "C20") (pin "2") (pinfunction "2_2") (pintype "input"))
      (node (ref "CN2") (pin "2") (pinfunction "2_2") (pintype "unspecified"))
      (node (ref "D1") (pin "1") (pinfunction "K_1") (pintype "unspecified"))
      (node (ref "U4") (pin "1") (pinfunction "IN_1") (pintype "unspecified"))
      (node (ref "U4") (pin "3") (pinfunction "EN_3") (pintype "unspecified"))
    )
    (net (code "76") (name "unconnected-(U2-EP-Pad9)") (class "Default")
      (node (ref "U2") (pin "9") (pinfunction "EP_9") (pintype "unspecified+no_connect"))
    )
    (net (code "77") (name "unconnected-(U4-NC-Pad4)") (class "Default")
      (node (ref "U4") (pin "4") (pinfunction "NC_4") (pintype "unspecified+no_connect"))
    )
    (net (code "78") (name "unconnected-(USB1-SBU1-PadA8)") (class "Default")
      (node (ref "USB1") (pin "A8") (pinfunction "SBU1_A8") (pintype "unspecified+no_connect"))
    )
    (net (code "79") (name "unconnected-(USB1-SBU2-PadB8)") (class "Default")
      (node (ref "USB1") (pin "B8") (pinfunction "SBU2_B8") (pintype "unspecified+no_connect"))
    )
  )
)
